# h-bridge-gate-driver.net
KiCad netlist of a schematic drawn in EAGLE
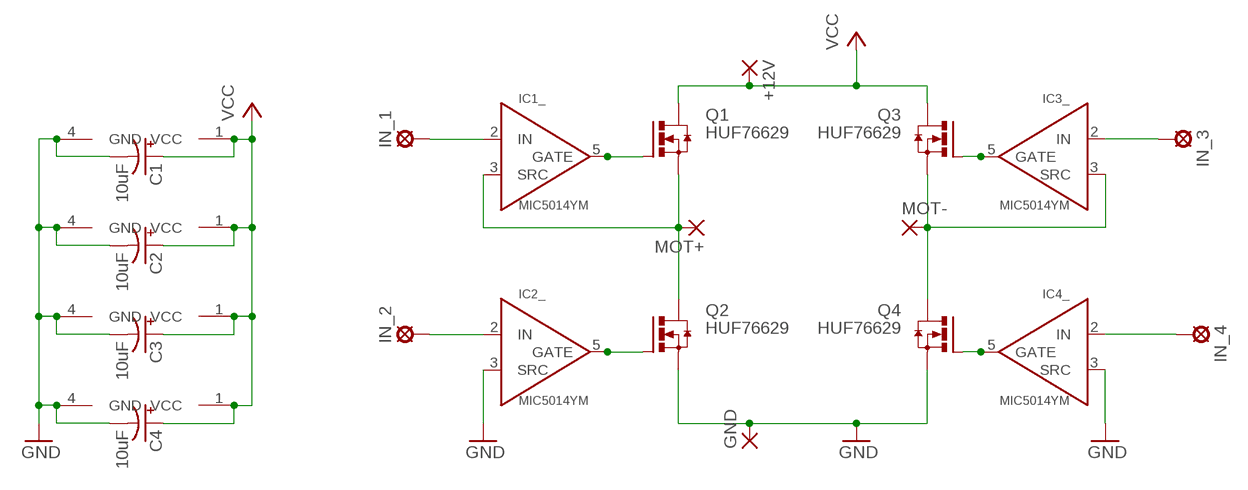
[diagram p0: schematic, sheet 1]

(export (version "E")
  (design (tool "Eeschema 10.0.6"))
  (components
    (comp (ref "+12V")
      (value "WIREPAD4,16O1,6")
      (footprint "eagle-import:4,16O1,6")
      (libsource (lib "eagle-import") (part "WIREPAD4,16O1,6"))
    )
    (comp (ref "C1")
      (value "10uF")
      (footprint "eagle-import:153CLV-0810")
      (libsource (lib "eagle-import") (part "CPOL-US153CLV-0810"))
    )
    (comp (ref "C2")
      (value "10uF")
      (footprint "eagle-import:153CLV-0810")
      (libsource (lib "eagle-import") (part "CPOL-US153CLV-0810"))
    )
    (comp (ref "C3")
      (value "10uF")
      (footprint "eagle-import:153CLV-0810")
      (libsource (lib "eagle-import") (part "CPOL-US153CLV-0810"))
    )
    (comp (ref "C4")
      (value "10uF")
      (footprint "eagle-import:153CLV-0810")
      (libsource (lib "eagle-import") (part "CPOL-US153CLV-0810"))
    )
    (comp (ref "GND")
      (value "WIREPAD4,16O1,6")
      (footprint "eagle-import:4,16O1,6")
      (libsource (lib "eagle-import") (part "WIREPAD4,16O1,6"))
    )
    (comp (ref "IC1")
      (value "MIC5014YM")
      (footprint "eagle-import:SO8")
      (libsource (lib "eagle-import") (part "MIC5014YM"))
    )
    (comp (ref "IC2")
      (value "MIC5014YM")
      (footprint "eagle-import:SO8")
      (libsource (lib "eagle-import") (part "MIC5014YM"))
    )
    (comp (ref "IC3")
      (value "MIC5014YM")
      (footprint "eagle-import:SO8")
      (libsource (lib "eagle-import") (part "MIC5014YM"))
    )
    (comp (ref "IC4")
      (value "MIC5014YM")
      (footprint "eagle-import:SO8")
      (libsource (lib "eagle-import") (part "MIC5014YM"))
    )
    (comp (ref "IN_1")
      (value "LSP11")
      (footprint "eagle-import:LSP11")
      (libsource (lib "eagle-import") (part "LSP11"))
    )
    (comp (ref "IN_2")
      (value "LSP11")
      (footprint "eagle-import:LSP11")
      (libsource (lib "eagle-import") (part "LSP11"))
    )
    (comp (ref "IN_3")
      (value "LSP11")
      (footprint "eagle-import:LSP11")
      (libsource (lib "eagle-import") (part "LSP11"))
    )
    (comp (ref "IN_4")
      (value "LSP11")
      (footprint "eagle-import:LSP11")
      (libsource (lib "eagle-import") (part "LSP11"))
    )
    (comp (ref "MOT+")
      (value "WIREPAD4,16O1,6")
      (footprint "eagle-import:4,16O1,6")
      (libsource (lib "eagle-import") (part "WIREPAD4,16O1,6"))
    )
    (comp (ref "MOT-")
      (value "WIREPAD4,16O1,6")
      (footprint "eagle-import:4,16O1,6")
      (libsource (lib "eagle-import") (part "WIREPAD4,16O1,6"))
    )
    (comp (ref "Q1")
      (value "HUF76629")
      (footprint "eagle-import:D-PAK_TO252")
      (libsource (lib "eagle-import") (part "HUF76629D3ST_F085D-PAK_TO252"))
    )
    (comp (ref "Q2")
      (value "HUF76629")
      (footprint "eagle-import:D-PAK_TO252")
      (libsource (lib "eagle-import") (part "HUF76629D3ST_F085D-PAK_TO252"))
    )
    (comp (ref "Q3")
      (value "HUF76629")
      (footprint "eagle-import:D-PAK_TO252")
      (libsource (lib "eagle-import") (part "HUF76629D3ST_F085D-PAK_TO252"))
    )
    (comp (ref "Q4")
      (value "HUF76629")
      (footprint "eagle-import:D-PAK_TO252")
      (libsource (lib "eagle-import") (part "HUF76629D3ST_F085D-PAK_TO252"))
    )
  )
  (nets
    (net (code "1") (name "GND") (class "Default")
      (node (ref "C1") (pin "-") (pinfunction "-_-") (pintype "passive"))
      (node (ref "C2") (pin "-") (pinfunction "-_-") (pintype "passive"))
      (node (ref "C3") (pin "-") (pinfunction "-_-") (pintype "passive"))
      (node (ref "C4") (pin "-") (pinfunction "-_-") (pintype "passive"))
      (node (ref "GND") (pin "1") (pinfunction "P_1") (pintype "passive"))
      (node (ref "IC1") (pin "4") (pinfunction "GND_4") (pintype "power_in"))
      (node (ref "IC2") (pin "3") (pinfunction "SRC_3") (pintype "input"))
      (node (ref "IC2") (pin "4") (pinfunction "GND_4") (pintype "power_in"))
      (node (ref "IC3") (pin "4") (pinfunction "GND_4") (pintype "power_in"))
      (node (ref "IC4") (pin "3") (pinfunction "SRC_3") (pintype "input"))
      (node (ref "IC4") (pin "4") (pinfunction "GND_4") (pintype "power_in"))
      (node (ref "Q2") (pin "3") (pinfunction "S_3") (pintype "passive"))
      (node (ref "Q4") (pin "3") (pinfunction "S_3") (pintype "passive"))
    )
    (net (code "2") (name "Net-(IC1B-GATE)") (class "Default")
      (node (ref "IC1") (pin "5") (pinfunction "GATE_5") (pintype "output"))
      (node (ref "Q1") (pin "1") (pinfunction "G_1") (pintype "passive"))
    )
    (net (code "3") (name "Net-(IC1B-IN)") (class "Default")
      (node (ref "IC1") (pin "2") (pinfunction "IN_2") (pintype "input"))
      (node (ref "IN_1") (pin "MP") (pinfunction "MP_MP") (pintype "passive"))
    )
    (net (code "4") (name "Net-(IC1B-SRC)") (class "Default")
      (node (ref "IC1") (pin "3") (pinfunction "SRC_3") (pintype "input"))
      (node (ref "MOT+") (pin "1") (pinfunction "P_1") (pintype "passive"))
      (node (ref "Q1") (pin "3") (pinfunction "S_3") (pintype "passive"))
      (node (ref "Q2") (pin "4") (pinfunction "D_4") (pintype "passive"))
    )
    (net (code "5") (name "Net-(IC2B-GATE)") (class "Default")
      (node (ref "IC2") (pin "5") (pinfunction "GATE_5") (pintype "output"))
      (node (ref "Q2") (pin "1") (pinfunction "G_1") (pintype "passive"))
    )
    (net (code "6") (name "Net-(IC2B-IN)") (class "Default")
      (node (ref "IC2") (pin "2") (pinfunction "IN_2") (pintype "input"))
      (node (ref "IN_2") (pin "MP") (pinfunction "MP_MP") (pintype "passive"))
    )
    (net (code "7") (name "Net-(IC3B-GATE)") (class "Default")
      (node (ref "IC3") (pin "5") (pinfunction "GATE_5") (pintype "output"))
      (node (ref "Q3") (pin "1") (pinfunction "G_1") (pintype "passive"))
    )
    (net (code "8") (name "Net-(IC3B-IN)") (class "Default")
      (node (ref "IC3") (pin "2") (pinfunction "IN_2") (pintype "input"))
      (node (ref "IN_3") (pin "MP") (pinfunction "MP_MP") (pintype "passive"))
    )
    (net (code "9") (name "Net-(IC3B-SRC)") (class "Default")
      (node (ref "IC3") (pin "3") (pinfunction "SRC_3") (pintype "input"))
      (node (ref "MOT-") (pin "1") (pinfunction "P_1") (pintype "passive"))
      (node (ref "Q3") (pin "3") (pinfunction "S_3") (pintype "passive"))
      (node (ref "Q4") (pin "4") (pinfunction "D_4") (pintype "passive"))
    )
    (net (code "10") (name "Net-(IC4B-GATE)") (class "Default")
      (node (ref "IC4") (pin "5") (pinfunction "GATE_5") (pintype "output"))
      (node (ref "Q4") (pin "1") (pinfunction "G_1") (pintype "passive"))
    )
    (net (code "11") (name "Net-(IC4B-IN)") (class "Default")
      (node (ref "IC4") (pin "2") (pinfunction "IN_2") (pintype "input"))
      (node (ref "IN_4") (pin "MP") (pinfunction "MP_MP") (pintype "passive"))
    )
    (net (code "12") (name "VCC") (class "Default")
      (node (ref "+12V") (pin "1") (pinfunction "P_1") (pintype "passive"))
      (node (ref "C1") (pin "+") (pinfunction "+_+") (pintype "passive"))
      (node (ref "C2") (pin "+") (pinfunction "+_+") (pintype "passive"))
      (node (ref "C3") (pin "+") (pinfunction "+_+") (pintype "passive"))
      (node (ref "C4") (pin "+") (pinfunction "+_+") (pintype "passive"))
      (node (ref "IC1") (pin "1") (pinfunction "VCC_1") (pintype "power_in"))
      (node (ref "IC2") (pin "1") (pinfunction "VCC_1") (pintype "power_in"))
      (node (ref "IC3") (pin "1") (pinfunction "VCC_1") (pintype "power_in"))
      (node (ref "IC4") (pin "1") (pinfunction "VCC_1") (pintype "power_in"))
      (node (ref "Q1") (pin "4") (pinfunction "D_4") (pintype "passive"))
      (node (ref "Q3") (pin "4") (pinfunction "D_4") (pintype "passive"))
    )
  )
)
